# Meshtastic-DIY_v1_03.net
KiCad netlist of a schematic drawn in EAGLE
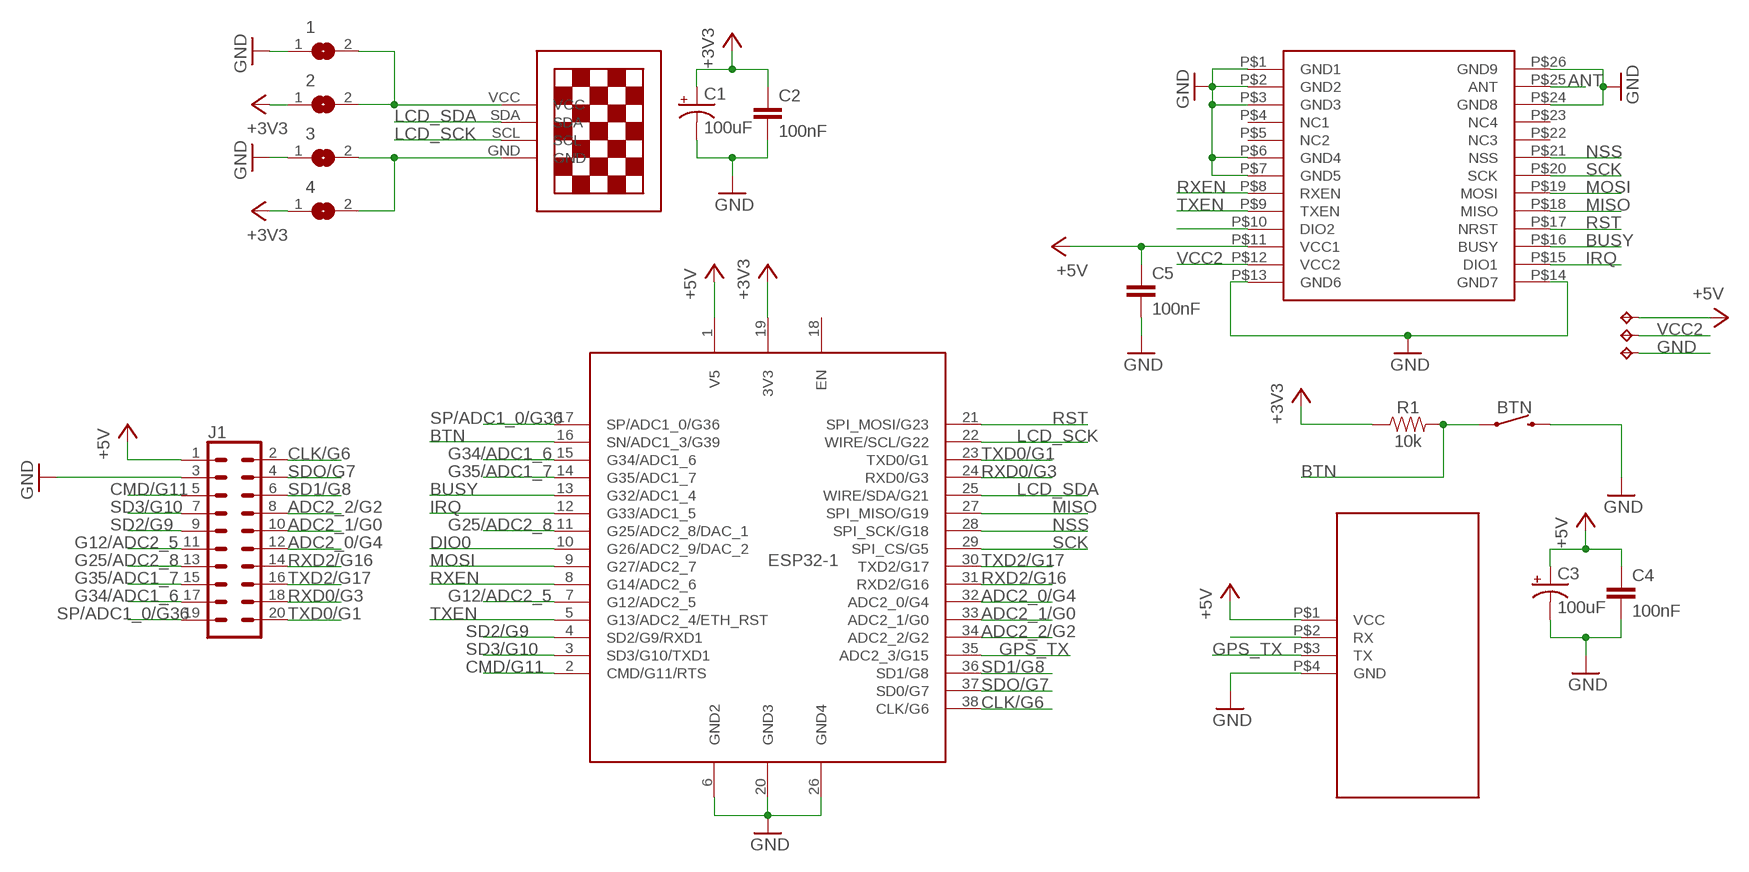
[diagram p0: schematic, sheet 1]

(export (version "E")
  (design (tool "Eeschema 10.0.6"))
  (components
    (comp (ref "1") (value "SJ") (footprint "eagle-import:SJ") (libsource (lib "eagle-import") (part "SJ")))
    (comp (ref "2") (value "SJ") (footprint "eagle-import:SJ") (libsource (lib "eagle-import") (part "SJ")))
    (comp (ref "3") (value "SJ") (footprint "eagle-import:SJ") (libsource (lib "eagle-import") (part "SJ")))
    (comp (ref "4") (value "SJ") (footprint "eagle-import:SJ") (libsource (lib "eagle-import") (part "SJ")))
    (comp (ref "BTN")
      (value "MOMENTARY-SWITCH-SPST-SMD-5.2MM")
      (footprint "eagle-import:TACTILE_SWITCH_SMD_5.2MM")
      (libsource (lib "eagle-import") (part "MOMENTARY-SWITCH-SPST-SMD-5.2MM"))
    )
    (comp (ref "C1")
      (value "100uF")
      (footprint "eagle-import:EIA7343")
      (libsource (lib "eagle-import") (part "100UF-POLAR-EIA7343-10V-10%(TANT)"))
    )
    (comp (ref "C2")
      (value "100nF")
      (footprint "eagle-import:0805")
      (libsource (lib "eagle-import") (part "0.33UF/330NF-0805-50V-10%"))
    )
    (comp (ref "C3")
      (value "100uF")
      (footprint "eagle-import:EIA7343")
      (libsource (lib "eagle-import") (part "100UF-POLAR-EIA7343-10V-10%(TANT)"))
    )
    (comp (ref "C4")
      (value "100nF")
      (footprint "eagle-import:0805")
      (libsource (lib "eagle-import") (part "0.33UF/330NF-0805-50V-10%"))
    )
    (comp (ref "C5")
      (value "100nF")
      (footprint "eagle-import:0805")
      (libsource (lib "eagle-import") (part "0.33UF/330NF-0805-50V-10%"))
    )
    (comp (ref "ESP32-1")
      (value "NODEMCU_ESP32_WROOM_32")
      (footprint "eagle-import:NODEMCU_ESP32_WROOM_32--38PINS")
      (libsource (lib "eagle-import") (part "NODEMCU_ESP32_WROOM_32"))
    )
    (comp (ref "J1")
      (value "CONN_10X2NOSILK")
      (footprint "eagle-import:2X10_NOSILK")
      (libsource (lib "eagle-import") (part "CONN_10X2NOSILK"))
    )
    (comp (ref "R1")
      (value "10k")
      (footprint "eagle-import:1210")
      (libsource (lib "eagle-import") (part "0.1OHM-1210-1/2W-1%"))
    )
    (comp (ref "TP1")
      (value "TPTP14SQ")
      (footprint "eagle-import:TP14SQ")
      (libsource (lib "eagle-import") (part "TPTP14SQ"))
    )
    (comp (ref "TP2")
      (value "TPTP14SQ")
      (footprint "eagle-import:TP14SQ")
      (libsource (lib "eagle-import") (part "TPTP14SQ"))
    )
    (comp (ref "TP3")
      (value "TPTP14SQ")
      (footprint "eagle-import:TP14SQ")
      (libsource (lib "eagle-import") (part "TPTP14SQ"))
    )
    (comp (ref "U$1")
      (value "13\"OLED13\"OLED")
      (footprint "eagle-import:1.3_OLED")
      (libsource (lib "eagle-import") (part "13{dblquote}OLED13{dblquote}OLED"))
    )
    (comp (ref "U$2")
      (value "E22-XXXMXXS")
      (footprint "eagle-import:E22-XXXMXXS")
      (libsource (lib "eagle-import") (part "E22-XXXMXXS"))
    )
    (comp (ref "U$3")
      (value "GPS-NEO")
      (footprint "eagle-import:GPS-NEO")
      (libsource (lib "eagle-import") (part "GPS-NEO"))
    )
  )
  (nets
    (net (code "1") (name "+3V3") (class "Default")
      (node (ref "2") (pin "1") (pinfunction "1_1") (pintype "passive"))
      (node (ref "4") (pin "1") (pinfunction "1_1") (pintype "passive"))
      (node (ref "C1") (pin "A") (pinfunction "+_A") (pintype "passive"))
      (node (ref "C2") (pin "1") (pinfunction "1_1") (pintype "passive"))
      (node (ref "ESP32-1") (pin "19") (pinfunction "3V3_19") (pintype "power_in"))
      (node (ref "R1") (pin "1") (pinfunction "1_1") (pintype "passive"))
    )
    (net (code "2") (name "+5V") (class "Default")
      (node (ref "C3") (pin "A") (pinfunction "+_A") (pintype "passive"))
      (node (ref "C4") (pin "1") (pinfunction "1_1") (pintype "passive"))
      (node (ref "C5") (pin "1") (pinfunction "1_1") (pintype "passive"))
      (node (ref "ESP32-1") (pin "1") (pinfunction "V5_1") (pintype "power_in"))
      (node (ref "J1") (pin "1") (pinfunction "1_1") (pintype "passive"))
      (node (ref "TP1") (pin "TP") (pinfunction "TP_TP") (pintype "input"))
      (node (ref "U$2") (pin "P$11") (pinfunction "VCC1_P$11") (pintype "bidirectional"))
      (node (ref "U$3") (pin "P$1") (pinfunction "VCC_P$1") (pintype "bidirectional"))
    )
    (net (code "3") (name "/ADC2_0{slash}G4") (class "Default")
      (node (ref "ESP32-1") (pin "32") (pinfunction "ADC2_0/G4_32") (pintype "bidirectional"))
      (node (ref "J1") (pin "12") (pinfunction "12_12") (pintype "passive"))
    )
    (net (code "4") (name "/ADC2_1{slash}G0") (class "Default")
      (node (ref "ESP32-1") (pin "33") (pinfunction "ADC2_1/G0_33") (pintype "bidirectional"))
      (node (ref "J1") (pin "10") (pinfunction "10_10") (pintype "passive"))
    )
    (net (code "5") (name "/ADC2_2{slash}G2") (class "Default")
      (node (ref "ESP32-1") (pin "34") (pinfunction "ADC2_2/G2_34") (pintype "bidirectional"))
      (node (ref "J1") (pin "8") (pinfunction "8_8") (pintype "passive"))
    )
    (net (code "6") (name "/ANT") (class "Default")
      (node (ref "U$2") (pin "P$25") (pinfunction "ANT_P$25") (pintype "bidirectional"))
    )
    (net (code "7") (name "/BTN") (class "Default")
      (node (ref "BTN") (pin "1") (pinfunction "1_1") (pintype "passive"))
      (node (ref "ESP32-1") (pin "16") (pinfunction "SN/ADC1_3/G39_16") (pintype "bidirectional"))
      (node (ref "R1") (pin "2") (pinfunction "2_2") (pintype "passive"))
    )
    (net (code "8") (name "/BUSY") (class "Default")
      (node (ref "ESP32-1") (pin "13") (pinfunction "G32/ADC1_4_13") (pintype "bidirectional"))
      (node (ref "U$2") (pin "P$16") (pinfunction "BUSY_P$16") (pintype "bidirectional"))
    )
    (net (code "9") (name "/CLK{slash}G6") (class "Default")
      (node (ref "ESP32-1") (pin "38") (pinfunction "CLK/G6_38") (pintype "bidirectional"))
      (node (ref "J1") (pin "2") (pinfunction "2_2") (pintype "passive"))
    )
    (net (code "10") (name "/CMD{slash}G11") (class "Default")
      (node (ref "ESP32-1") (pin "2") (pinfunction "CMD/G11/RTS_2") (pintype "power_in"))
      (node (ref "J1") (pin "5") (pinfunction "5_5") (pintype "passive"))
    )
    (net (code "11") (name "/DIO0") (class "Default")
      (node (ref "ESP32-1") (pin "10") (pinfunction "G26/ADC2_9/DAC_2_10") (pintype "bidirectional"))
    )
    (net (code "12") (name "/G12{slash}ADC2_5") (class "Default")
      (node (ref "ESP32-1") (pin "7") (pinfunction "G12/ADC2_5_7") (pintype "bidirectional"))
      (node (ref "J1") (pin "11") (pinfunction "11_11") (pintype "passive"))
    )
    (net (code "13") (name "/G25{slash}ADC2_8") (class "Default")
      (node (ref "ESP32-1") (pin "11") (pinfunction "G25/ADC2_8/DAC_1_11") (pintype "bidirectional"))
      (node (ref "J1") (pin "13") (pinfunction "13_13") (pintype "passive"))
    )
    (net (code "14") (name "/G34{slash}ADC1_6") (class "Default")
      (node (ref "ESP32-1") (pin "15") (pinfunction "G34/ADC1_6_15") (pintype "bidirectional"))
      (node (ref "J1") (pin "17") (pinfunction "17_17") (pintype "passive"))
    )
    (net (code "15") (name "/G35{slash}ADC1_7") (class "Default")
      (node (ref "ESP32-1") (pin "14") (pinfunction "G35/ADC1_7_14") (pintype "bidirectional"))
      (node (ref "J1") (pin "15") (pinfunction "15_15") (pintype "passive"))
    )
    (net (code "16") (name "/GPS_TX") (class "Default")
      (node (ref "ESP32-1") (pin "35") (pinfunction "ADC2_3/G15_35") (pintype "bidirectional"))
      (node (ref "U$3") (pin "P$3") (pinfunction "TX_P$3") (pintype "bidirectional"))
    )
    (net (code "17") (name "/IRQ") (class "Default")
      (node (ref "ESP32-1") (pin "12") (pinfunction "G33/ADC1_5_12") (pintype "bidirectional"))
      (node (ref "U$2") (pin "P$15") (pinfunction "DIO1_P$15") (pintype "bidirectional"))
    )
    (net (code "18") (name "/LCD_SCK") (class "Default")
      (node (ref "ESP32-1") (pin "22") (pinfunction "WIRE/SCL/G22_22") (pintype "bidirectional"))
      (node (ref "U$1") (pin "SCL") (pinfunction "SCL_SCL") (pintype "bidirectional"))
    )
    (net (code "19") (name "/LCD_SDA") (class "Default")
      (node (ref "ESP32-1") (pin "25") (pinfunction "WIRE/SDA/G21_25") (pintype "bidirectional"))
      (node (ref "U$1") (pin "SDA") (pinfunction "SDA_SDA") (pintype "bidirectional"))
    )
    (net (code "20") (name "/MISO") (class "Default")
      (node (ref "ESP32-1") (pin "27") (pinfunction "SPI_MISO/G19_27") (pintype "bidirectional"))
      (node (ref "U$2") (pin "P$18") (pinfunction "MISO_P$18") (pintype "bidirectional"))
    )
    (net (code "21") (name "/MOSI") (class "Default")
      (node (ref "ESP32-1") (pin "9") (pinfunction "G27/ADC2_7_9") (pintype "bidirectional"))
      (node (ref "U$2") (pin "P$19") (pinfunction "MOSI_P$19") (pintype "bidirectional"))
    )
    (net (code "22") (name "/NSS") (class "Default")
      (node (ref "ESP32-1") (pin "28") (pinfunction "SPI_SCK/G18_28") (pintype "bidirectional"))
      (node (ref "U$2") (pin "P$21") (pinfunction "NSS_P$21") (pintype "bidirectional"))
    )
    (net (code "23") (name "/RST") (class "Default")
      (node (ref "ESP32-1") (pin "21") (pinfunction "SPI_MOSI/G23_21") (pintype "bidirectional"))
      (node (ref "U$2") (pin "P$17") (pinfunction "NRST_P$17") (pintype "bidirectional"))
    )
    (net (code "24") (name "/RXD0{slash}G3") (class "Default")
      (node (ref "ESP32-1") (pin "24") (pinfunction "RXD0/G3_24") (pintype "bidirectional"))
      (node (ref "J1") (pin "18") (pinfunction "18_18") (pintype "passive"))
    )
    (net (code "25") (name "/RXD2{slash}G16") (class "Default")
      (node (ref "ESP32-1") (pin "31") (pinfunction "RXD2/G16_31") (pintype "bidirectional"))
      (node (ref "J1") (pin "14") (pinfunction "14_14") (pintype "passive"))
    )
    (net (code "26") (name "/RXEN") (class "Default")
      (node (ref "ESP32-1") (pin "8") (pinfunction "G14/ADC2_6_8") (pintype "bidirectional"))
      (node (ref "U$2") (pin "P$8") (pinfunction "RXEN_P$8") (pintype "bidirectional"))
    )
    (net (code "27") (name "/SCK") (class "Default")
      (node (ref "ESP32-1") (pin "29") (pinfunction "SPI_CS/G5_29") (pintype "bidirectional"))
      (node (ref "U$2") (pin "P$20") (pinfunction "SCK_P$20") (pintype "bidirectional"))
    )
    (net (code "28") (name "/SD1{slash}G8") (class "Default")
      (node (ref "ESP32-1") (pin "36") (pinfunction "SD1/G8_36") (pintype "bidirectional"))
      (node (ref "J1") (pin "6") (pinfunction "6_6") (pintype "passive"))
    )
    (net (code "29") (name "/SD2{slash}G9") (class "Default")
      (node (ref "ESP32-1") (pin "4") (pinfunction "SD2/G9/RXD1_4") (pintype "bidirectional"))
      (node (ref "J1") (pin "9") (pinfunction "9_9") (pintype "passive"))
    )
    (net (code "30") (name "/SD3{slash}G10") (class "Default")
      (node (ref "ESP32-1") (pin "3") (pinfunction "SD3/G10/TXD1_3") (pintype "bidirectional"))
      (node (ref "J1") (pin "7") (pinfunction "7_7") (pintype "passive"))
    )
    (net (code "31") (name "/SDO{slash}G7") (class "Default")
      (node (ref "ESP32-1") (pin "37") (pinfunction "SD0/G7_37") (pintype "bidirectional"))
      (node (ref "J1") (pin "4") (pinfunction "4_4") (pintype "passive"))
    )
    (net (code "32") (name "/SP{slash}ADC1_0{slash}G36") (class "Default")
      (node (ref "ESP32-1") (pin "17") (pinfunction "SP/ADC1_0/G36_17") (pintype "bidirectional"))
      (node (ref "J1") (pin "19") (pinfunction "19_19") (pintype "passive"))
    )
    (net (code "33") (name "/TXD0{slash}G1") (class "Default")
      (node (ref "ESP32-1") (pin "23") (pinfunction "TXD0/G1_23") (pintype "bidirectional"))
      (node (ref "J1") (pin "20") (pinfunction "20_20") (pintype "passive"))
    )
    (net (code "34") (name "/TXD2{slash}G17") (class "Default")
      (node (ref "ESP32-1") (pin "30") (pinfunction "TXD2/G17_30") (pintype "bidirectional"))
      (node (ref "J1") (pin "16") (pinfunction "16_16") (pintype "passive"))
    )
    (net (code "35") (name "/TXEN") (class "Default")
      (node (ref "ESP32-1") (pin "5") (pinfunction "G13/ADC2_4/ETH_RST_5") (pintype "bidirectional"))
      (node (ref "U$2") (pin "P$9") (pinfunction "TXEN_P$9") (pintype "bidirectional"))
    )
    (net (code "36") (name "/VCC2") (class "Default")
      (node (ref "TP2") (pin "TP") (pinfunction "TP_TP") (pintype "input"))
      (node (ref "U$2") (pin "P$12") (pinfunction "VCC2_P$12") (pintype "bidirectional"))
    )
    (net (code "37") (name "GND") (class "Default")
      (node (ref "1") (pin "1") (pinfunction "1_1") (pintype "passive"))
      (node (ref "3") (pin "1") (pinfunction "1_1") (pintype "passive"))
      (node (ref "BTN") (pin "3") (pinfunction "2_3") (pintype "passive"))
      (node (ref "C1") (pin "C") (pinfunction "-_C") (pintype "passive"))
      (node (ref "C2") (pin "2") (pinfunction "2_2") (pintype "passive"))
      (node (ref "C3") (pin "C") (pinfunction "-_C") (pintype "passive"))
      (node (ref "C4") (pin "2") (pinfunction "2_2") (pintype "passive"))
      (node (ref "C5") (pin "2") (pinfunction "2_2") (pintype "passive"))
      (node (ref "ESP32-1") (pin "20") (pinfunction "GND3_20") (pintype "power_in"))
      (node (ref "ESP32-1") (pin "26") (pinfunction "GND4_26") (pintype "power_in"))
      (node (ref "ESP32-1") (pin "6") (pinfunction "GND2_6") (pintype "power_in"))
      (node (ref "J1") (pin "3") (pinfunction "3_3") (pintype "passive"))
      (node (ref "TP3") (pin "TP") (pinfunction "TP_TP") (pintype "input"))
      (node (ref "U$2") (pin "P$1") (pinfunction "GND1_P$1") (pintype "bidirectional"))
      (node (ref "U$2") (pin "P$13") (pinfunction "GND6_P$13") (pintype "bidirectional"))
      (node (ref "U$2") (pin "P$14") (pinfunction "GND7_P$14") (pintype "bidirectional"))
      (node (ref "U$2") (pin "P$2") (pinfunction "GND2_P$2") (pintype "bidirectional"))
      (node (ref "U$2") (pin "P$24") (pinfunction "GND8_P$24") (pintype "bidirectional"))
      (node (ref "U$2") (pin "P$26") (pinfunction "GND9_P$26") (pintype "bidirectional"))
      (node (ref "U$2") (pin "P$3") (pinfunction "GND3_P$3") (pintype "bidirectional"))
      (node (ref "U$2") (pin "P$6") (pinfunction "GND4_P$6") (pintype "bidirectional"))
      (node (ref "U$2") (pin "P$7") (pinfunction "GND5_P$7") (pintype "bidirectional"))
      (node (ref "U$3") (pin "P$4") (pinfunction "GND_P$4") (pintype "bidirectional"))
    )
    (net (code "38") (name "Net-(1-Pad2)") (class "Default")
      (node (ref "1") (pin "2") (pinfunction "2_2") (pintype "passive"))
      (node (ref "2") (pin "2") (pinfunction "2_2") (pintype "passive"))
      (node (ref "U$1") (pin "VCC") (pinfunction "VCC_VCC") (pintype "bidirectional"))
    )
    (net (code "39") (name "Net-(3-Pad2)") (class "Default")
      (node (ref "3") (pin "2") (pinfunction "2_2") (pintype "passive"))
      (node (ref "4") (pin "2") (pinfunction "2_2") (pintype "passive"))
      (node (ref "U$1") (pin "GND") (pinfunction "GND_GND") (pintype "bidirectional"))
    )
    (net (code "40") (name "unconnected-(ESP32-1-EN-Pad18)") (class "Default")
      (node (ref "ESP32-1") (pin "18") (pinfunction "EN_18") (pintype "bidirectional"))
    )
    (net (code "41") (name "unconnected-(U$2-DIO2-PadP$10)") (class "Default")
      (node (ref "U$2") (pin "P$10") (pinfunction "DIO2_P$10") (pintype "bidirectional"))
    )
    (net (code "42") (name "unconnected-(U$2-NC1-PadP$4)") (class "Default")
      (node (ref "U$2") (pin "P$4") (pinfunction "NC1_P$4") (pintype "bidirectional"))
    )
    (net (code "43") (name "unconnected-(U$2-NC2-PadP$5)") (class "Default")
      (node (ref "U$2") (pin "P$5") (pinfunction "NC2_P$5") (pintype "bidirectional"))
    )
    (net (code "44") (name "unconnected-(U$2-NC3-PadP$22)") (class "Default")
      (node (ref "U$2") (pin "P$22") (pinfunction "NC3_P$22") (pintype "bidirectional"))
    )
    (net (code "45") (name "unconnected-(U$2-NC4-PadP$23)") (class "Default")
      (node (ref "U$2") (pin "P$23") (pinfunction "NC4_P$23") (pintype "bidirectional"))
    )
    (net (code "46") (name "unconnected-(U$3-RX-PadP$2)") (class "Default")
      (node (ref "U$3") (pin "P$2") (pinfunction "RX_P$2") (pintype "bidirectional"))
    )
  )
)
